# LEDA_Arcade_Controller_Touch_sensor.net
KiCad netlist of a schematic drawn in EasyEDA
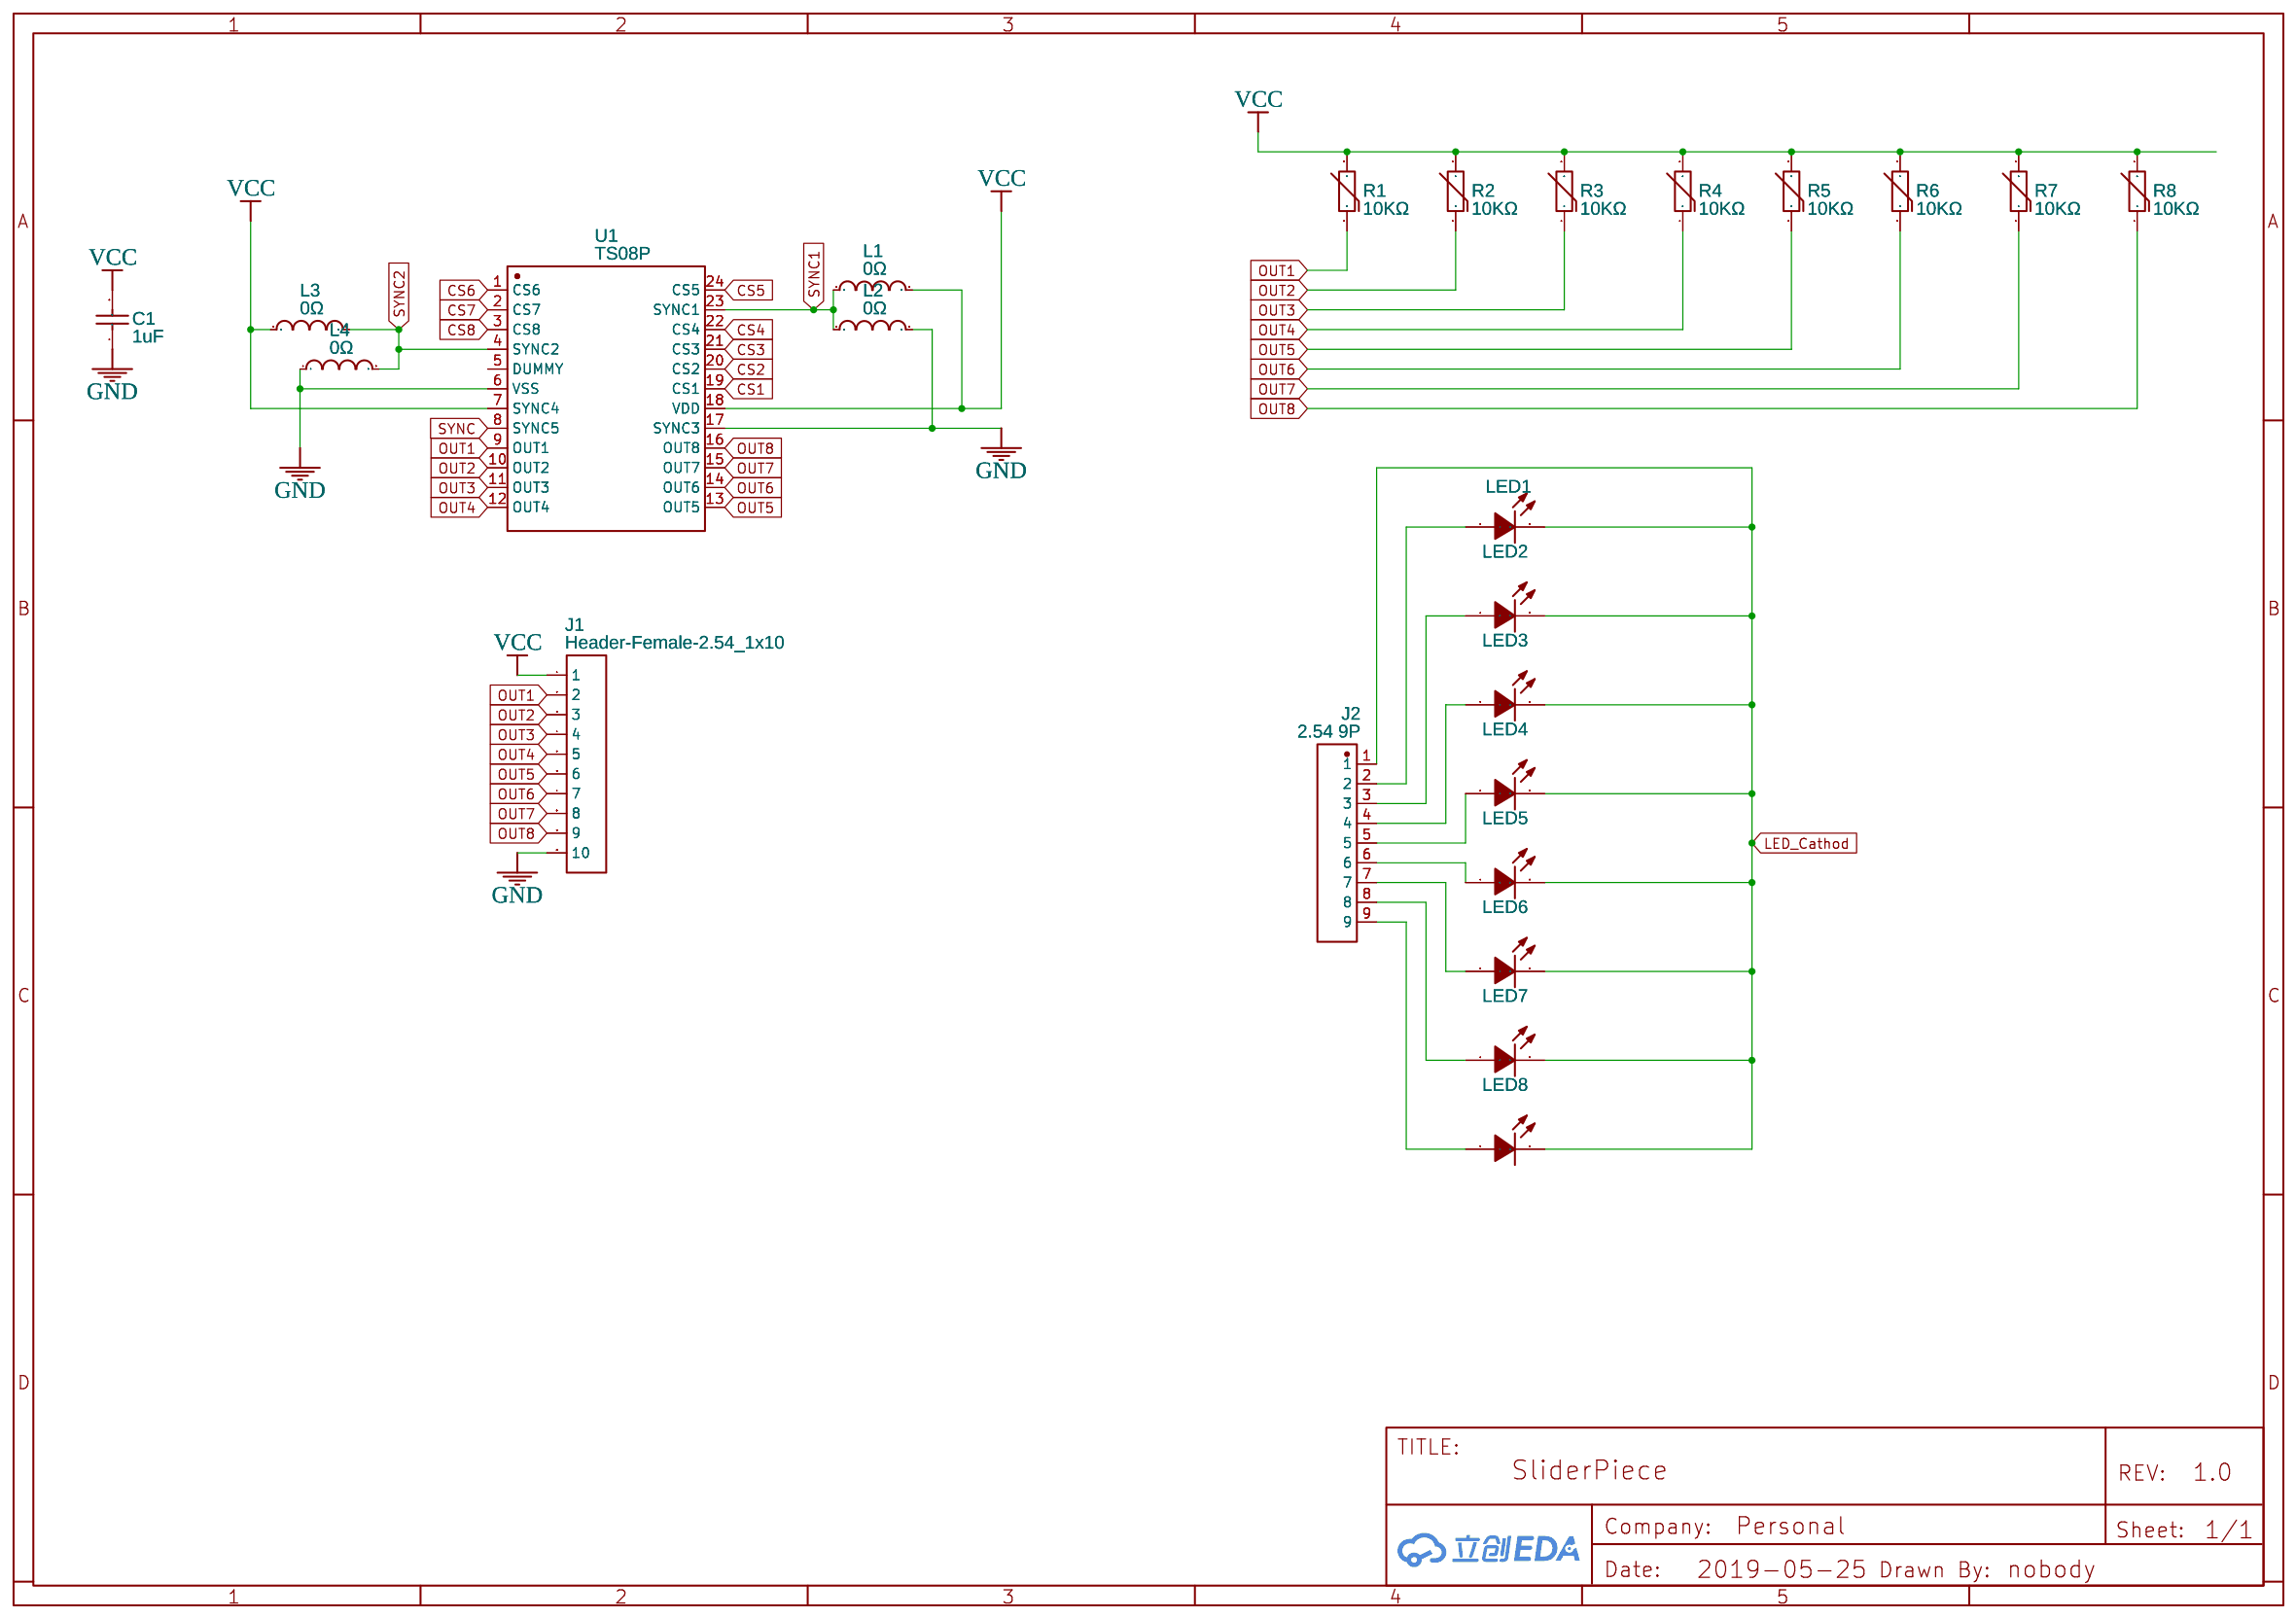
[diagram p0: schematic sheet]

(export (version "E")
  (design (tool "Eeschema 10.0.6"))
  (components
    (comp (ref "C1")
      (value "1uF")
      (fields
        (field (name "BOM_Manufacturer Part") "UMK107AB7105KA-T")
        (field (name "BOM_Supplier Part") "C105174")
      )
      (libsource (lib "") (part "UMK107AB7105KA-T"))
    )
    (comp (ref "J1")
      (value "Header-Female-2.54_1x10")
      (fields
        (field (name "BOM_Manufacturer Part") "2.54mm 1*10P Straight Female header Gold-plated")
        (field (name "BOM_Supplier Part") "C35445")
      )
      (libsource (lib "") (part "Unknown_280_385"))
    )
    (comp (ref "J2")
      (value "2.54 9P")
      (fields (field (name "BOM_Manufacturer Part") "?"))
      (libsource (lib "") (part "Unknown_670_420"))
    )
    (comp (ref "L1")
      (value "0Ω")
      (fields
        (field (name "BOM_Manufacturer Part") "CBG160808U000T")
        (field (name "BOM_Supplier Part") "C43163")
      )
      (libsource (lib "") (part "CBG160808U000T"))
    )
    (comp (ref "L2")
      (value "0Ω")
      (fields
        (field (name "BOM_Manufacturer Part") "CBG160808U000T")
        (field (name "BOM_Supplier Part") "C43163")
      )
      (libsource (lib "") (part "CBG160808U000T"))
    )
    (comp (ref "L3")
      (value "0Ω")
      (fields
        (field (name "BOM_Manufacturer Part") "CBG160808U000T")
        (field (name "BOM_Supplier Part") "C43163")
      )
      (libsource (lib "") (part "CBG160808U000T_1"))
    )
    (comp (ref "L4")
      (value "0Ω")
      (fields
        (field (name "BOM_Manufacturer Part") "CBG160808U000T")
        (field (name "BOM_Supplier Part") "C43163")
      )
      (libsource (lib "") (part "CBG160808U000T_1"))
    )
    (comp (ref "LED1")
      (value "333-2SUGC/S400-A5")
      (fields (field (name "BOM_Supplier Part") "C125761"))
      (libsource (lib "") (part "Unknown_755_255"))
    )
    (comp (ref "LED2")
      (value "333-2SUGC/S400-A5")
      (fields (field (name "BOM_Supplier Part") "C125761"))
      (libsource (lib "") (part "Unknown_755_300"))
    )
    (comp (ref "LED3")
      (value "333-2SUGC/S400-A5")
      (fields (field (name "BOM_Supplier Part") "C125761"))
      (libsource (lib "") (part "Unknown_755_345"))
    )
    (comp (ref "LED4")
      (value "333-2SUGC/S400-A5")
      (fields (field (name "BOM_Supplier Part") "C125761"))
      (libsource (lib "") (part "Unknown_755_390"))
    )
    (comp (ref "LED5")
      (value "333-2SUGC/S400-A5")
      (fields (field (name "BOM_Supplier Part") "C125761"))
      (libsource (lib "") (part "Unknown_755_435"))
    )
    (comp (ref "LED6")
      (value "333-2SUGC/S400-A5")
      (fields (field (name "BOM_Supplier Part") "C125761"))
      (libsource (lib "") (part "Unknown_755_480"))
    )
    (comp (ref "LED7")
      (value "333-2SUGC/S400-A5")
      (fields (field (name "BOM_Supplier Part") "C125761"))
      (libsource (lib "") (part "Unknown_755_525"))
    )
    (comp (ref "LED8")
      (value "333-2SUGC/S400-A5")
      (fields (field (name "BOM_Supplier Part") "C125761"))
      (libsource (lib "") (part "Unknown_755_570"))
    )
    (comp (ref "R1")
      (value "10KΩ")
      (fields
        (field (name "BOM_Manufacturer Part") "CMFA103J35000HANT")
        (field (name "BOM_Supplier Part") "C107464")
      )
      (libsource (lib "") (part "CMFA103J35000HANT"))
    )
    (comp (ref "R2")
      (value "10KΩ")
      (fields
        (field (name "BOM_Manufacturer Part") "CMFA103J35000HANT")
        (field (name "BOM_Supplier Part") "C107464")
      )
      (libsource (lib "") (part "CMFA103J35000HANT"))
    )
    (comp (ref "R3")
      (value "10KΩ")
      (fields
        (field (name "BOM_Manufacturer Part") "CMFA103J35000HANT")
        (field (name "BOM_Supplier Part") "C107464")
      )
      (libsource (lib "") (part "CMFA103J35000HANT"))
    )
    (comp (ref "R4")
      (value "10KΩ")
      (fields
        (field (name "BOM_Manufacturer Part") "CMFA103J35000HANT")
        (field (name "BOM_Supplier Part") "C107464")
      )
      (libsource (lib "") (part "CMFA103J35000HANT"))
    )
    (comp (ref "R5")
      (value "10KΩ")
      (fields
        (field (name "BOM_Manufacturer Part") "CMFA103J35000HANT")
        (field (name "BOM_Supplier Part") "C107464")
      )
      (libsource (lib "") (part "CMFA103J35000HANT"))
    )
    (comp (ref "R6")
      (value "10KΩ")
      (fields
        (field (name "BOM_Manufacturer Part") "CMFA103J35000HANT")
        (field (name "BOM_Supplier Part") "C107464")
      )
      (libsource (lib "") (part "CMFA103J35000HANT"))
    )
    (comp (ref "R7")
      (value "10KΩ")
      (fields
        (field (name "BOM_Manufacturer Part") "CMFA103J35000HANT")
        (field (name "BOM_Supplier Part") "C107464")
      )
      (libsource (lib "") (part "CMFA103J35000HANT"))
    )
    (comp (ref "R8")
      (value "10KΩ")
      (fields
        (field (name "BOM_Manufacturer Part") "CMFA103J35000HANT")
        (field (name "BOM_Supplier Part") "C107464")
      )
      (libsource (lib "") (part "CMFA103J35000HANT"))
    )
    (comp (ref "U1")
      (value "TS08P")
      (fields (field (name "BOM_Supplier Part") "C132388"))
      (libsource (lib "") (part "Unknown_300_195"))
    )
  )
  (nets
    (net (code "1") (name "CS1") (class "Default")
      (node (ref "U1") (pin "19") (pinfunction "CS1_19") (pintype "unspecified"))
    )
    (net (code "2") (name "CS2") (class "Default")
      (node (ref "U1") (pin "20") (pinfunction "CS2_20") (pintype "unspecified"))
    )
    (net (code "3") (name "CS3") (class "Default")
      (node (ref "U1") (pin "21") (pinfunction "CS3_21") (pintype "unspecified"))
    )
    (net (code "4") (name "CS4") (class "Default")
      (node (ref "U1") (pin "22") (pinfunction "CS4_22") (pintype "unspecified"))
    )
    (net (code "5") (name "CS5") (class "Default")
      (node (ref "U1") (pin "24") (pinfunction "CS5_24") (pintype "unspecified"))
    )
    (net (code "6") (name "CS6") (class "Default")
      (node (ref "U1") (pin "1") (pinfunction "CS6_1") (pintype "unspecified"))
    )
    (net (code "7") (name "CS7") (class "Default")
      (node (ref "U1") (pin "2") (pinfunction "CS7_2") (pintype "unspecified"))
    )
    (net (code "8") (name "CS8") (class "Default")
      (node (ref "U1") (pin "3") (pinfunction "CS8_3") (pintype "unspecified"))
    )
    (net (code "9") (name "GND") (class "Default")
      (node (ref "C1") (pin "1") (pinfunction "1_1") (pintype "input"))
      (node (ref "J1") (pin "10") (pinfunction "10_10") (pintype "input"))
      (node (ref "L2") (pin "2") (pinfunction "2_2") (pintype "unspecified"))
      (node (ref "L4") (pin "1") (pinfunction "1_1") (pintype "unspecified"))
      (node (ref "U1") (pin "17") (pinfunction "SYNC3_17") (pintype "unspecified"))
      (node (ref "U1") (pin "6") (pinfunction "VSS_6") (pintype "unspecified"))
    )
    (net (code "10") (name "LED_Cathod") (class "Default")
      (node (ref "J2") (pin "1") (pinfunction "1_1") (pintype "unspecified"))
      (node (ref "LED1") (pin "2") (pinfunction "K_2") (pintype "unspecified"))
      (node (ref "LED2") (pin "2") (pinfunction "K_2") (pintype "unspecified"))
      (node (ref "LED3") (pin "2") (pinfunction "K_2") (pintype "unspecified"))
      (node (ref "LED4") (pin "2") (pinfunction "K_2") (pintype "unspecified"))
      (node (ref "LED5") (pin "2") (pinfunction "K_2") (pintype "unspecified"))
      (node (ref "LED6") (pin "2") (pinfunction "K_2") (pintype "unspecified"))
      (node (ref "LED7") (pin "2") (pinfunction "K_2") (pintype "unspecified"))
      (node (ref "LED8") (pin "2") (pinfunction "K_2") (pintype "unspecified"))
    )
    (net (code "11") (name "Net-(LED1-A)") (class "Default")
      (node (ref "J2") (pin "2") (pinfunction "2_2") (pintype "unspecified"))
      (node (ref "LED1") (pin "1") (pinfunction "A_1") (pintype "unspecified"))
    )
    (net (code "12") (name "Net-(LED2-A)") (class "Default")
      (node (ref "J2") (pin "3") (pinfunction "3_3") (pintype "unspecified"))
      (node (ref "LED2") (pin "1") (pinfunction "A_1") (pintype "unspecified"))
    )
    (net (code "13") (name "Net-(LED3-A)") (class "Default")
      (node (ref "J2") (pin "4") (pinfunction "4_4") (pintype "unspecified"))
      (node (ref "LED3") (pin "1") (pinfunction "A_1") (pintype "unspecified"))
    )
    (net (code "14") (name "Net-(LED4-A)") (class "Default")
      (node (ref "J2") (pin "5") (pinfunction "5_5") (pintype "unspecified"))
      (node (ref "LED4") (pin "1") (pinfunction "A_1") (pintype "unspecified"))
    )
    (net (code "15") (name "Net-(LED5-A)") (class "Default")
      (node (ref "J2") (pin "6") (pinfunction "6_6") (pintype "unspecified"))
      (node (ref "LED5") (pin "1") (pinfunction "A_1") (pintype "unspecified"))
    )
    (net (code "16") (name "Net-(LED6-A)") (class "Default")
      (node (ref "J2") (pin "7") (pinfunction "7_7") (pintype "unspecified"))
      (node (ref "LED6") (pin "1") (pinfunction "A_1") (pintype "unspecified"))
    )
    (net (code "17") (name "Net-(LED7-A)") (class "Default")
      (node (ref "J2") (pin "8") (pinfunction "8_8") (pintype "unspecified"))
      (node (ref "LED7") (pin "1") (pinfunction "A_1") (pintype "unspecified"))
    )
    (net (code "18") (name "Net-(LED8-A)") (class "Default")
      (node (ref "J2") (pin "9") (pinfunction "9_9") (pintype "unspecified"))
      (node (ref "LED8") (pin "1") (pinfunction "A_1") (pintype "unspecified"))
    )
    (net (code "19") (name "OUT1") (class "Default")
      (node (ref "J1") (pin "2") (pinfunction "2_2") (pintype "input"))
      (node (ref "R1") (pin "1") (pinfunction "1_1") (pintype "input"))
      (node (ref "U1") (pin "9") (pinfunction "OUT1_9") (pintype "unspecified"))
    )
    (net (code "20") (name "OUT2") (class "Default")
      (node (ref "J1") (pin "3") (pinfunction "3_3") (pintype "input"))
      (node (ref "R2") (pin "1") (pinfunction "1_1") (pintype "input"))
      (node (ref "U1") (pin "10") (pinfunction "OUT2_10") (pintype "unspecified"))
    )
    (net (code "21") (name "OUT3") (class "Default")
      (node (ref "J1") (pin "4") (pinfunction "4_4") (pintype "input"))
      (node (ref "R3") (pin "1") (pinfunction "1_1") (pintype "input"))
      (node (ref "U1") (pin "11") (pinfunction "OUT3_11") (pintype "unspecified"))
    )
    (net (code "22") (name "OUT4") (class "Default")
      (node (ref "J1") (pin "5") (pinfunction "5_5") (pintype "input"))
      (node (ref "R4") (pin "1") (pinfunction "1_1") (pintype "input"))
      (node (ref "U1") (pin "12") (pinfunction "OUT4_12") (pintype "unspecified"))
    )
    (net (code "23") (name "OUT5") (class "Default")
      (node (ref "J1") (pin "6") (pinfunction "6_6") (pintype "input"))
      (node (ref "R5") (pin "1") (pinfunction "1_1") (pintype "input"))
      (node (ref "U1") (pin "13") (pinfunction "OUT5_13") (pintype "unspecified"))
    )
    (net (code "24") (name "OUT6") (class "Default")
      (node (ref "J1") (pin "7") (pinfunction "7_7") (pintype "input"))
      (node (ref "R6") (pin "1") (pinfunction "1_1") (pintype "input"))
      (node (ref "U1") (pin "14") (pinfunction "OUT6_14") (pintype "unspecified"))
    )
    (net (code "25") (name "OUT7") (class "Default")
      (node (ref "J1") (pin "8") (pinfunction "8_8") (pintype "input"))
      (node (ref "R7") (pin "1") (pinfunction "1_1") (pintype "input"))
      (node (ref "U1") (pin "15") (pinfunction "OUT7_15") (pintype "unspecified"))
    )
    (net (code "26") (name "OUT8") (class "Default")
      (node (ref "J1") (pin "9") (pinfunction "9_9") (pintype "input"))
      (node (ref "R8") (pin "1") (pinfunction "1_1") (pintype "input"))
      (node (ref "U1") (pin "16") (pinfunction "OUT8_16") (pintype "unspecified"))
    )
    (net (code "27") (name "SYNC") (class "Default")
      (node (ref "U1") (pin "8") (pinfunction "SYNC5_8") (pintype "unspecified"))
    )
    (net (code "28") (name "SYNC1") (class "Default")
      (node (ref "L1") (pin "1") (pinfunction "1_1") (pintype "unspecified"))
      (node (ref "L2") (pin "1") (pinfunction "1_1") (pintype "unspecified"))
      (node (ref "U1") (pin "23") (pinfunction "SYNC1_23") (pintype "unspecified"))
    )
    (net (code "29") (name "SYNC2") (class "Default")
      (node (ref "L3") (pin "2") (pinfunction "2_2") (pintype "unspecified"))
      (node (ref "L4") (pin "2") (pinfunction "2_2") (pintype "unspecified"))
      (node (ref "U1") (pin "4") (pinfunction "SYNC2_4") (pintype "unspecified"))
    )
    (net (code "30") (name "VCC") (class "Default")
      (node (ref "C1") (pin "2") (pinfunction "2_2") (pintype "input"))
      (node (ref "J1") (pin "1") (pinfunction "1_1") (pintype "input"))
      (node (ref "L1") (pin "2") (pinfunction "2_2") (pintype "unspecified"))
      (node (ref "L3") (pin "1") (pinfunction "1_1") (pintype "unspecified"))
      (node (ref "R1") (pin "2") (pinfunction "2_2") (pintype "input"))
      (node (ref "R2") (pin "2") (pinfunction "2_2") (pintype "input"))
      (node (ref "R3") (pin "2") (pinfunction "2_2") (pintype "input"))
      (node (ref "R4") (pin "2") (pinfunction "2_2") (pintype "input"))
      (node (ref "R5") (pin "2") (pinfunction "2_2") (pintype "input"))
      (node (ref "R6") (pin "2") (pinfunction "2_2") (pintype "input"))
      (node (ref "R7") (pin "2") (pinfunction "2_2") (pintype "input"))
      (node (ref "R8") (pin "2") (pinfunction "2_2") (pintype "input"))
      (node (ref "U1") (pin "18") (pinfunction "VDD_18") (pintype "unspecified"))
      (node (ref "U1") (pin "7") (pinfunction "SYNC4_7") (pintype "unspecified"))
    )
    (net (code "31") (name "unconnected-(U1-DUMMY-Pad5)") (class "Default")
      (node (ref "U1") (pin "5") (pinfunction "DUMMY_5") (pintype "unspecified"))
    )
  )
)
